# ADCs.net
KiCad netlist of a schematic drawn in Altium Designer
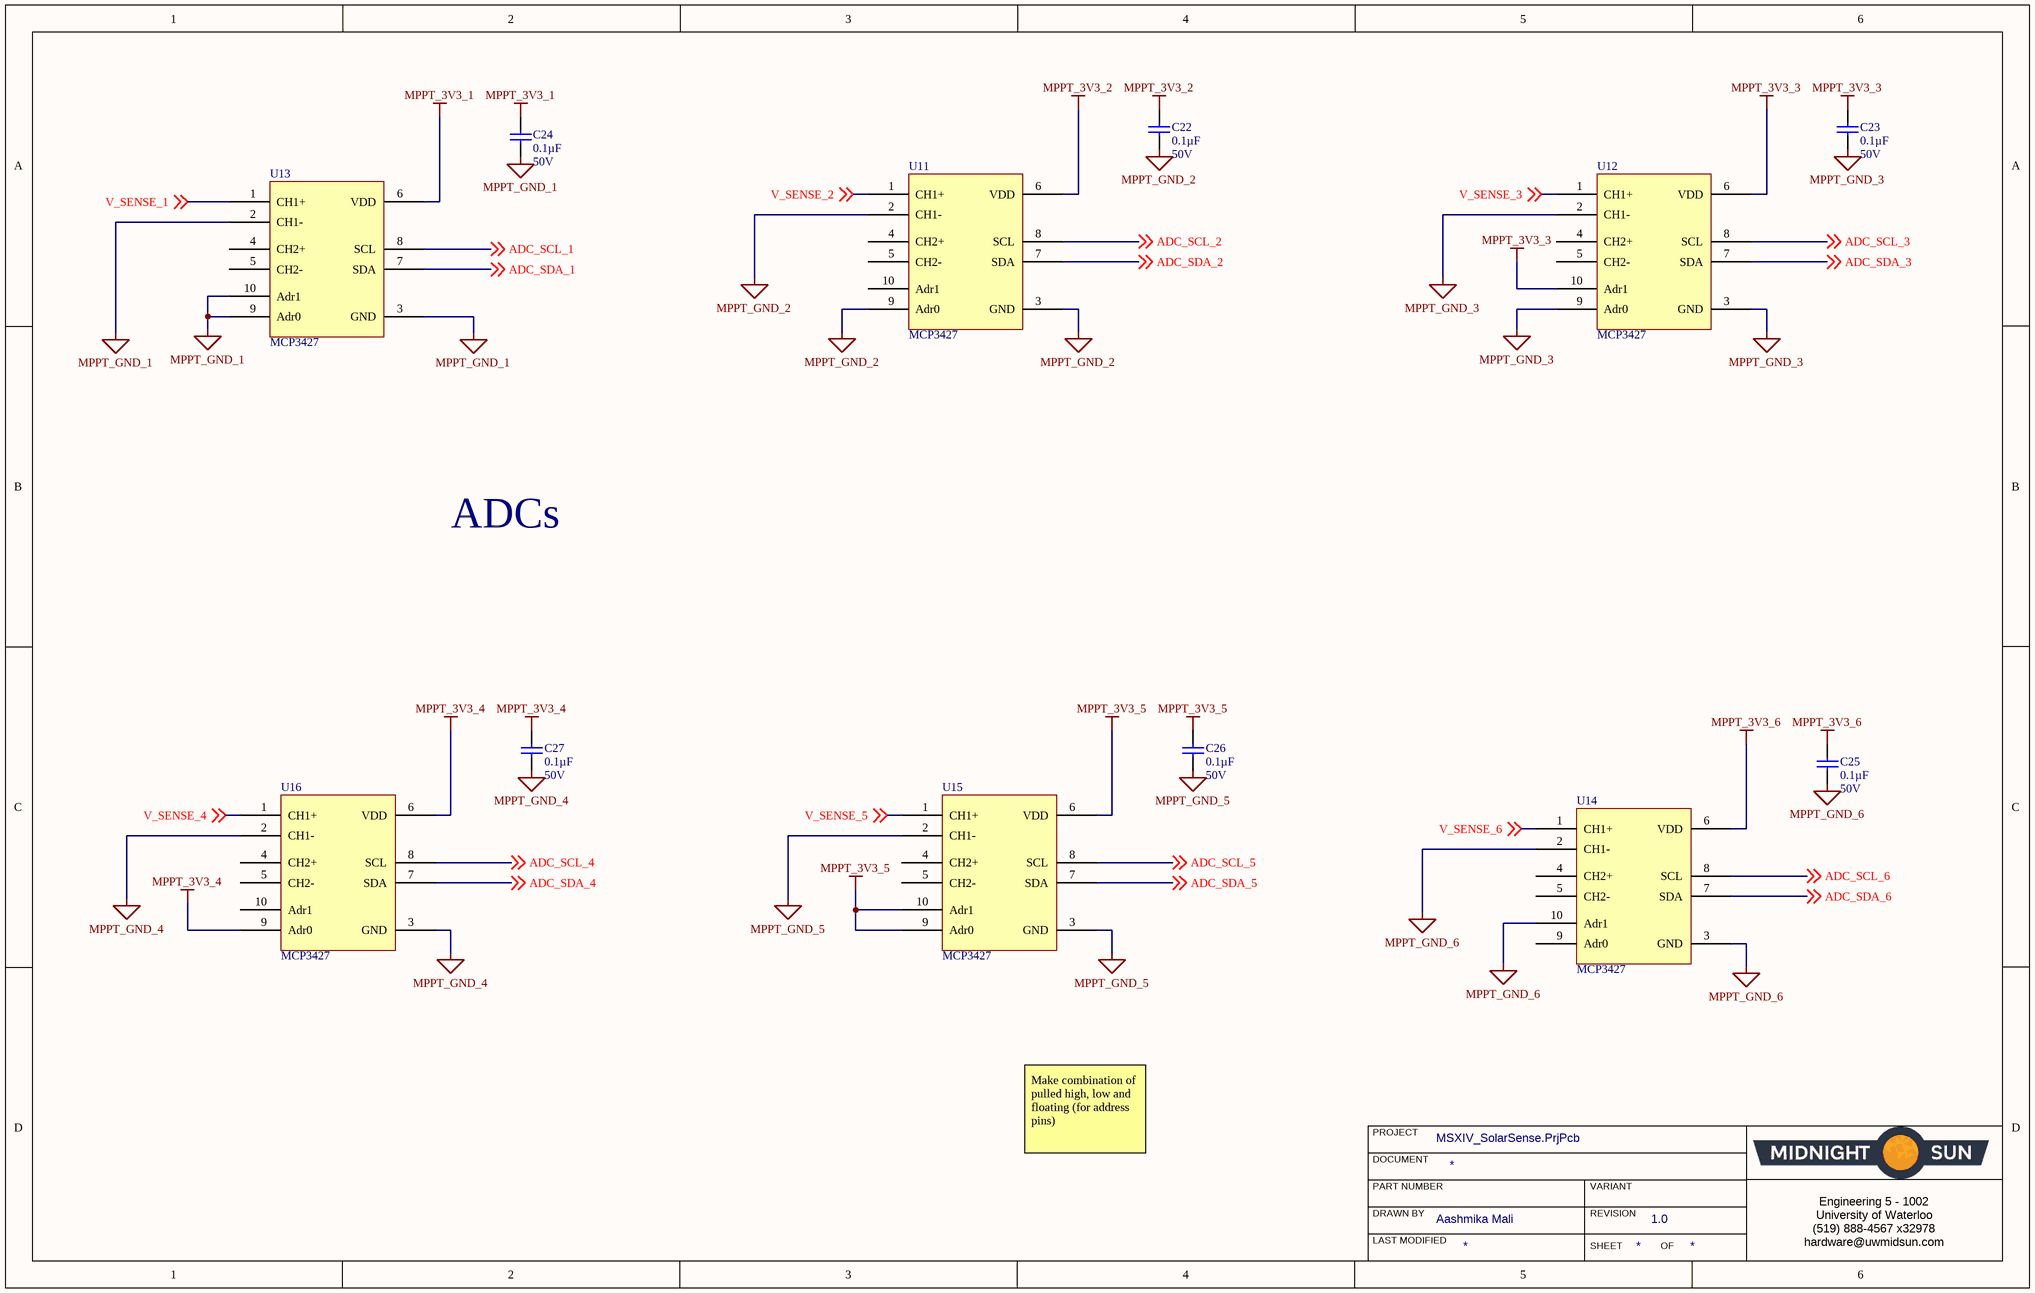
[diagram p0: ADCs.SchDoc]

(export (version "E")
  (design (tool "Eeschema 10.0.6"))
  (components
    (comp (ref "C22")
      (value "CAP CER 0.1UF 50V 10% X7R 0603")
      (footprint "CAP, 0603")
      (description "0.10µF ±10% 50V Ceramic Capacitor X7R 0603 (1608 Metric)")
      (fields
        (field (name "TOLERANCE") "±10%")
        (field (name "CAPACITANCE") "0.1µF")
        (field (name "VOLTAGE") "50V")
      )
      (libsource (lib "Schematic Diagrams") (part "CAP CER 0.1UF 50V 10% X7R 0603"))
    )
    (comp (ref "C23")
      (value "CAP CER 0.1UF 50V 10% X7R 0603")
      (footprint "CAP, 0603")
      (description "0.10µF ±10% 50V Ceramic Capacitor X7R 0603 (1608 Metric)")
      (fields
        (field (name "TOLERANCE") "±10%")
        (field (name "CAPACITANCE") "0.1µF")
        (field (name "VOLTAGE") "50V")
      )
      (libsource (lib "Schematic Diagrams") (part "CAP CER 0.1UF 50V 10% X7R 0603"))
    )
    (comp (ref "C24")
      (value "CAP CER 0.1UF 50V 10% X7R 0603")
      (footprint "CAP, 0603")
      (description "0.10µF ±10% 50V Ceramic Capacitor X7R 0603 (1608 Metric)")
      (fields
        (field (name "TOLERANCE") "±10%")
        (field (name "CAPACITANCE") "0.1µF")
        (field (name "VOLTAGE") "50V")
      )
      (libsource (lib "Schematic Diagrams") (part "CAP CER 0.1UF 50V 10% X7R 0603"))
    )
    (comp (ref "C25")
      (value "CAP CER 0.1UF 50V 10% X7R 0603")
      (footprint "CAP, 0603")
      (description "0.10µF ±10% 50V Ceramic Capacitor X7R 0603 (1608 Metric)")
      (fields
        (field (name "TOLERANCE") "±10%")
        (field (name "CAPACITANCE") "0.1µF")
        (field (name "VOLTAGE") "50V")
      )
      (libsource (lib "Schematic Diagrams") (part "CAP CER 0.1UF 50V 10% X7R 0603"))
    )
    (comp (ref "C26")
      (value "CAP CER 0.1UF 50V 10% X7R 0603")
      (footprint "CAP, 0603")
      (description "0.10µF ±10% 50V Ceramic Capacitor X7R 0603 (1608 Metric)")
      (fields
        (field (name "TOLERANCE") "±10%")
        (field (name "CAPACITANCE") "0.1µF")
        (field (name "VOLTAGE") "50V")
      )
      (libsource (lib "Schematic Diagrams") (part "CAP CER 0.1UF 50V 10% X7R 0603"))
    )
    (comp (ref "C27")
      (value "CAP CER 0.1UF 50V 10% X7R 0603")
      (footprint "CAP, 0603")
      (description "0.10µF ±10% 50V Ceramic Capacitor X7R 0603 (1608 Metric)")
      (fields
        (field (name "TOLERANCE") "±10%")
        (field (name "CAPACITANCE") "0.1µF")
        (field (name "VOLTAGE") "50V")
      )
      (libsource (lib "Schematic Diagrams") (part "CAP CER 0.1UF 50V 10% X7R 0603"))
    )
    (comp (ref "U11")
      (value "IC ADC MCP3427 10MSOP")
      (footprint "IC ADC MCP3427")
      (description "16 Bit Analog to Digital Converter 2 Input 1 Sigma-Delta 10-MSOP")
      (fields
        (field (name "MANUFACTURER") "Microchip Technology")
        (field (name "MANUFACTURER PART NUMBER") "MCP3427-E/UN")
        (field (name "BASE PART NUMBER") "MCP3427")
      )
      (libsource (lib "Schematic Diagrams") (part "IC ADC MCP3427 10MSOP"))
    )
    (comp (ref "U12")
      (value "IC ADC MCP3427 10MSOP")
      (footprint "IC ADC MCP3427")
      (description "16 Bit Analog to Digital Converter 2 Input 1 Sigma-Delta 10-MSOP")
      (fields
        (field (name "MANUFACTURER") "Microchip Technology")
        (field (name "MANUFACTURER PART NUMBER") "MCP3427-E/UN")
        (field (name "BASE PART NUMBER") "MCP3427")
      )
      (libsource (lib "Schematic Diagrams") (part "IC ADC MCP3427 10MSOP"))
    )
    (comp (ref "U13")
      (value "IC ADC MCP3427 10MSOP")
      (footprint "IC ADC MCP3427")
      (description "16 Bit Analog to Digital Converter 2 Input 1 Sigma-Delta 10-MSOP")
      (fields
        (field (name "MANUFACTURER") "Microchip Technology")
        (field (name "MANUFACTURER PART NUMBER") "MCP3427-E/UN")
        (field (name "BASE PART NUMBER") "MCP3427")
      )
      (libsource (lib "Schematic Diagrams") (part "IC ADC MCP3427 10MSOP"))
    )
    (comp (ref "U14")
      (value "IC ADC MCP3427 10MSOP")
      (footprint "IC ADC MCP3427")
      (description "16 Bit Analog to Digital Converter 2 Input 1 Sigma-Delta 10-MSOP")
      (fields
        (field (name "MANUFACTURER") "Microchip Technology")
        (field (name "MANUFACTURER PART NUMBER") "MCP3427-E/UN")
        (field (name "BASE PART NUMBER") "MCP3427")
      )
      (libsource (lib "Schematic Diagrams") (part "IC ADC MCP3427 10MSOP"))
    )
    (comp (ref "U15")
      (value "IC ADC MCP3427 10MSOP")
      (footprint "IC ADC MCP3427")
      (description "16 Bit Analog to Digital Converter 2 Input 1 Sigma-Delta 10-MSOP")
      (fields
        (field (name "MANUFACTURER") "Microchip Technology")
        (field (name "MANUFACTURER PART NUMBER") "MCP3427-E/UN")
        (field (name "BASE PART NUMBER") "MCP3427")
      )
      (libsource (lib "Schematic Diagrams") (part "IC ADC MCP3427 10MSOP"))
    )
    (comp (ref "U16")
      (value "IC ADC MCP3427 10MSOP")
      (footprint "IC ADC MCP3427")
      (description "16 Bit Analog to Digital Converter 2 Input 1 Sigma-Delta 10-MSOP")
      (fields
        (field (name "MANUFACTURER") "Microchip Technology")
        (field (name "MANUFACTURER PART NUMBER") "MCP3427-E/UN")
        (field (name "BASE PART NUMBER") "MCP3427")
      )
      (libsource (lib "Schematic Diagrams") (part "IC ADC MCP3427 10MSOP"))
    )
  )
  (nets
    (net (code "1") (name "ADC_SCL_1") (class "Default")
      (node (ref "U13") (pin "8") (pinfunction "SCL_8") (pintype "passive"))
    )
    (net (code "2") (name "ADC_SCL_2") (class "Default")
      (node (ref "U11") (pin "8") (pinfunction "SCL_8") (pintype "passive"))
    )
    (net (code "3") (name "ADC_SCL_3") (class "Default")
      (node (ref "U12") (pin "8") (pinfunction "SCL_8") (pintype "passive"))
    )
    (net (code "4") (name "ADC_SCL_4") (class "Default")
      (node (ref "U16") (pin "8") (pinfunction "SCL_8") (pintype "passive"))
    )
    (net (code "5") (name "ADC_SCL_5") (class "Default")
      (node (ref "U15") (pin "8") (pinfunction "SCL_8") (pintype "passive"))
    )
    (net (code "6") (name "ADC_SCL_6") (class "Default")
      (node (ref "U14") (pin "8") (pinfunction "SCL_8") (pintype "passive"))
    )
    (net (code "7") (name "ADC_SDA_1") (class "Default")
      (node (ref "U13") (pin "7") (pinfunction "SDA_7") (pintype "passive"))
    )
    (net (code "8") (name "ADC_SDA_2") (class "Default")
      (node (ref "U11") (pin "7") (pinfunction "SDA_7") (pintype "passive"))
    )
    (net (code "9") (name "ADC_SDA_3") (class "Default")
      (node (ref "U12") (pin "7") (pinfunction "SDA_7") (pintype "passive"))
    )
    (net (code "10") (name "ADC_SDA_4") (class "Default")
      (node (ref "U16") (pin "7") (pinfunction "SDA_7") (pintype "passive"))
    )
    (net (code "11") (name "ADC_SDA_5") (class "Default")
      (node (ref "U15") (pin "7") (pinfunction "SDA_7") (pintype "passive"))
    )
    (net (code "12") (name "ADC_SDA_6") (class "Default")
      (node (ref "U14") (pin "7") (pinfunction "SDA_7") (pintype "passive"))
    )
    (net (code "13") (name "MPPT_3V3_1") (class "Default")
      (node (ref "C24") (pin "1") (pinfunction "1_1") (pintype "passive"))
      (node (ref "U13") (pin "6") (pinfunction "VDD_6") (pintype "passive"))
    )
    (net (code "14") (name "MPPT_3V3_2") (class "Default")
      (node (ref "C22") (pin "1") (pinfunction "1_1") (pintype "passive"))
      (node (ref "U11") (pin "6") (pinfunction "VDD_6") (pintype "passive"))
    )
    (net (code "15") (name "MPPT_3V3_3") (class "Default")
      (node (ref "C23") (pin "1") (pinfunction "1_1") (pintype "passive"))
      (node (ref "U12") (pin "10") (pinfunction "Adr1_10") (pintype "passive"))
      (node (ref "U12") (pin "6") (pinfunction "VDD_6") (pintype "passive"))
    )
    (net (code "16") (name "MPPT_3V3_4") (class "Default")
      (node (ref "C27") (pin "1") (pinfunction "1_1") (pintype "passive"))
      (node (ref "U16") (pin "6") (pinfunction "VDD_6") (pintype "passive"))
      (node (ref "U16") (pin "9") (pinfunction "Adr0_9") (pintype "passive"))
    )
    (net (code "17") (name "MPPT_3V3_5") (class "Default")
      (node (ref "C26") (pin "1") (pinfunction "1_1") (pintype "passive"))
      (node (ref "U15") (pin "10") (pinfunction "Adr1_10") (pintype "passive"))
      (node (ref "U15") (pin "6") (pinfunction "VDD_6") (pintype "passive"))
      (node (ref "U15") (pin "9") (pinfunction "Adr0_9") (pintype "passive"))
    )
    (net (code "18") (name "MPPT_3V3_6") (class "Default")
      (node (ref "C25") (pin "1") (pinfunction "1_1") (pintype "passive"))
      (node (ref "U14") (pin "6") (pinfunction "VDD_6") (pintype "passive"))
    )
    (net (code "19") (name "MPPT_GND_1") (class "Default")
      (node (ref "C24") (pin "2") (pinfunction "2_2") (pintype "passive"))
      (node (ref "U13") (pin "10") (pinfunction "Adr1_10") (pintype "passive"))
      (node (ref "U13") (pin "2") (pinfunction "CH1-_2") (pintype "passive"))
      (node (ref "U13") (pin "3") (pinfunction "GND_3") (pintype "passive"))
      (node (ref "U13") (pin "9") (pinfunction "Adr0_9") (pintype "passive"))
    )
    (net (code "20") (name "MPPT_GND_2") (class "Default")
      (node (ref "C22") (pin "2") (pinfunction "2_2") (pintype "passive"))
      (node (ref "U11") (pin "2") (pinfunction "CH1-_2") (pintype "passive"))
      (node (ref "U11") (pin "3") (pinfunction "GND_3") (pintype "passive"))
      (node (ref "U11") (pin "9") (pinfunction "Adr0_9") (pintype "passive"))
    )
    (net (code "21") (name "MPPT_GND_3") (class "Default")
      (node (ref "C23") (pin "2") (pinfunction "2_2") (pintype "passive"))
      (node (ref "U12") (pin "2") (pinfunction "CH1-_2") (pintype "passive"))
      (node (ref "U12") (pin "3") (pinfunction "GND_3") (pintype "passive"))
      (node (ref "U12") (pin "9") (pinfunction "Adr0_9") (pintype "passive"))
    )
    (net (code "22") (name "MPPT_GND_4") (class "Default")
      (node (ref "C27") (pin "2") (pinfunction "2_2") (pintype "passive"))
      (node (ref "U16") (pin "2") (pinfunction "CH1-_2") (pintype "passive"))
      (node (ref "U16") (pin "3") (pinfunction "GND_3") (pintype "passive"))
    )
    (net (code "23") (name "MPPT_GND_5") (class "Default")
      (node (ref "C26") (pin "2") (pinfunction "2_2") (pintype "passive"))
      (node (ref "U15") (pin "2") (pinfunction "CH1-_2") (pintype "passive"))
      (node (ref "U15") (pin "3") (pinfunction "GND_3") (pintype "passive"))
    )
    (net (code "24") (name "MPPT_GND_6") (class "Default")
      (node (ref "C25") (pin "2") (pinfunction "2_2") (pintype "passive"))
      (node (ref "U14") (pin "10") (pinfunction "Adr1_10") (pintype "passive"))
      (node (ref "U14") (pin "2") (pinfunction "CH1-_2") (pintype "passive"))
      (node (ref "U14") (pin "3") (pinfunction "GND_3") (pintype "passive"))
    )
    (net (code "25") (name "V_SENSE_1") (class "Default")
      (node (ref "U13") (pin "1") (pinfunction "CH1+_1") (pintype "passive"))
    )
    (net (code "26") (name "V_SENSE_2") (class "Default")
      (node (ref "U11") (pin "1") (pinfunction "CH1+_1") (pintype "passive"))
    )
    (net (code "27") (name "V_SENSE_3") (class "Default")
      (node (ref "U12") (pin "1") (pinfunction "CH1+_1") (pintype "passive"))
    )
    (net (code "28") (name "V_SENSE_4") (class "Default")
      (node (ref "U16") (pin "1") (pinfunction "CH1+_1") (pintype "passive"))
    )
    (net (code "29") (name "V_SENSE_5") (class "Default")
      (node (ref "U15") (pin "1") (pinfunction "CH1+_1") (pintype "passive"))
    )
    (net (code "30") (name "V_SENSE_6") (class "Default")
      (node (ref "U14") (pin "1") (pinfunction "CH1+_1") (pintype "passive"))
    )
    (net (code "31") (name "unconnected-(U11-Adr1-Pad10)") (class "Default")
      (node (ref "U11") (pin "10") (pinfunction "Adr1_10") (pintype "passive"))
    )
    (net (code "32") (name "unconnected-(U11-CH2+-Pad4)") (class "Default")
      (node (ref "U11") (pin "4") (pinfunction "CH2+_4") (pintype "passive"))
    )
    (net (code "33") (name "unconnected-(U11-CH2--Pad5)") (class "Default")
      (node (ref "U11") (pin "5") (pinfunction "CH2-_5") (pintype "passive"))
    )
    (net (code "34") (name "unconnected-(U12-CH2+-Pad4)") (class "Default")
      (node (ref "U12") (pin "4") (pinfunction "CH2+_4") (pintype "passive"))
    )
    (net (code "35") (name "unconnected-(U12-CH2--Pad5)") (class "Default")
      (node (ref "U12") (pin "5") (pinfunction "CH2-_5") (pintype "passive"))
    )
    (net (code "36") (name "unconnected-(U13-CH2+-Pad4)") (class "Default")
      (node (ref "U13") (pin "4") (pinfunction "CH2+_4") (pintype "passive"))
    )
    (net (code "37") (name "unconnected-(U13-CH2--Pad5)") (class "Default")
      (node (ref "U13") (pin "5") (pinfunction "CH2-_5") (pintype "passive"))
    )
    (net (code "38") (name "unconnected-(U14-Adr0-Pad9)") (class "Default")
      (node (ref "U14") (pin "9") (pinfunction "Adr0_9") (pintype "passive"))
    )
    (net (code "39") (name "unconnected-(U14-CH2+-Pad4)") (class "Default")
      (node (ref "U14") (pin "4") (pinfunction "CH2+_4") (pintype "passive"))
    )
    (net (code "40") (name "unconnected-(U14-CH2--Pad5)") (class "Default")
      (node (ref "U14") (pin "5") (pinfunction "CH2-_5") (pintype "passive"))
    )
    (net (code "41") (name "unconnected-(U15-CH2+-Pad4)") (class "Default")
      (node (ref "U15") (pin "4") (pinfunction "CH2+_4") (pintype "passive"))
    )
    (net (code "42") (name "unconnected-(U15-CH2--Pad5)") (class "Default")
      (node (ref "U15") (pin "5") (pinfunction "CH2-_5") (pintype "passive"))
    )
    (net (code "43") (name "unconnected-(U16-Adr1-Pad10)") (class "Default")
      (node (ref "U16") (pin "10") (pinfunction "Adr1_10") (pintype "passive"))
    )
    (net (code "44") (name "unconnected-(U16-CH2+-Pad4)") (class "Default")
      (node (ref "U16") (pin "4") (pinfunction "CH2+_4") (pintype "passive"))
    )
    (net (code "45") (name "unconnected-(U16-CH2--Pad5)") (class "Default")
      (node (ref "U16") (pin "5") (pinfunction "CH2-_5") (pintype "passive"))
    )
  )
)
